# test1.net
KiCad netlist of a schematic drawn in EAGLE
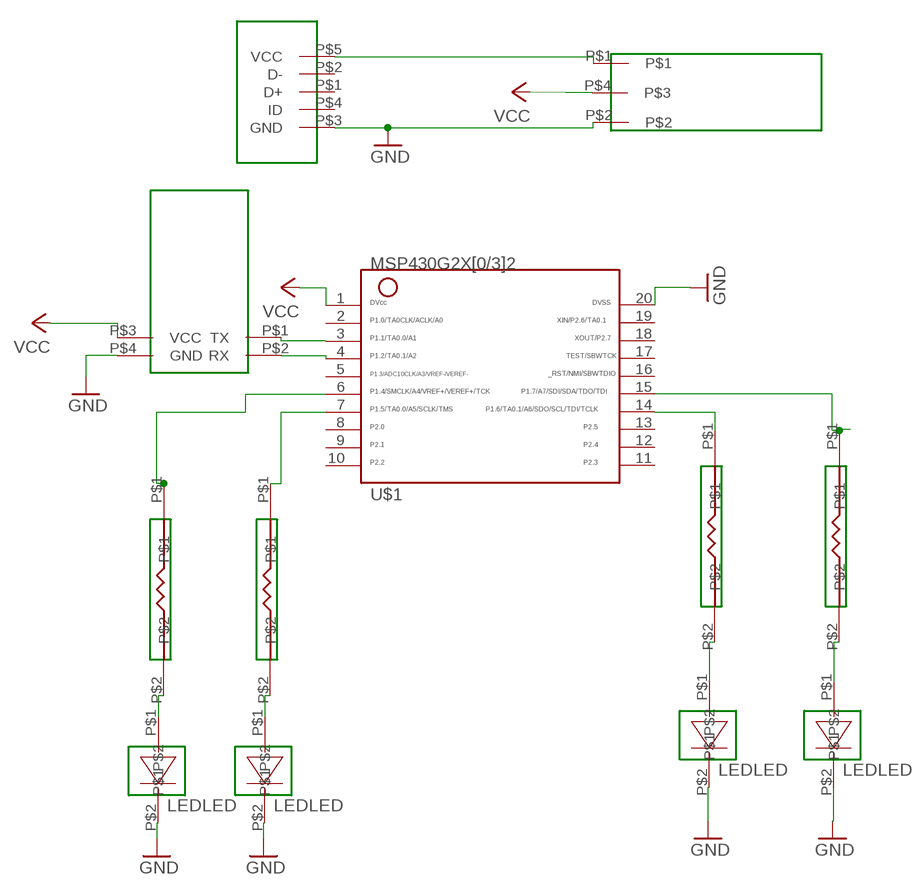
[diagram p0: schematic, sheet 1]

(export (version "E")
  (design (tool "Eeschema 10.0.6"))
  (components
    (comp (ref "U$1")
      (value "MSP430G553MSP430G2553")
      (footprint "eagle-import:MSP430G553")
      (libsource (lib "eagle-import") (part "MSP430G553MSP430G2553"))
    )
    (comp (ref "U$2")
      (value "RN41RN41")
      (footprint "eagle-import:RN41")
      (libsource (lib "eagle-import") (part "RN41RN41"))
    )
    (comp (ref "U$3")
      (value "USBUSB")
      (footprint "eagle-import:USB")
      (libsource (lib "eagle-import") (part "USBUSB"))
    )
    (comp (ref "U$4")
      (value "LEDLED")
      (footprint "eagle-import:LED")
      (libsource (lib "eagle-import") (part "LEDLED"))
    )
    (comp (ref "U$5")
      (value "LEDLED")
      (footprint "eagle-import:LED")
      (libsource (lib "eagle-import") (part "LEDLED"))
    )
    (comp (ref "U$6")
      (value "LEDLED")
      (footprint "eagle-import:LED")
      (libsource (lib "eagle-import") (part "LEDLED"))
    )
    (comp (ref "U$7")
      (value "LEDLED")
      (footprint "eagle-import:LED")
      (libsource (lib "eagle-import") (part "LEDLED"))
    )
    (comp (ref "U$8")
      (value "LMC3V3LMC3V3")
      (footprint "eagle-import:LMC3V3")
      (libsource (lib "eagle-import") (part "LMC3V3LMC3V3"))
    )
    (comp (ref "U$9")
      (value "1KOHM1KOHM")
      (footprint "eagle-import:1KOHM")
      (libsource (lib "eagle-import") (part "1KOHM1KOHM"))
    )
    (comp (ref "U$10")
      (value "1KOHM1KOHM")
      (footprint "eagle-import:1KOHM")
      (libsource (lib "eagle-import") (part "1KOHM1KOHM"))
    )
    (comp (ref "U$11")
      (value "1KOHM1KOHM")
      (footprint "eagle-import:1KOHM")
      (libsource (lib "eagle-import") (part "1KOHM1KOHM"))
    )
    (comp (ref "U$12")
      (value "1KOHM1KOHM")
      (footprint "eagle-import:1KOHM")
      (libsource (lib "eagle-import") (part "1KOHM1KOHM"))
    )
  )
  (nets
    (net (code "1") (name "GND") (class "Default")
      (node (ref "U$1") (pin "20") (pinfunction "20_20") (pintype "bidirectional"))
      (node (ref "U$2") (pin "P$4") (pinfunction "GND_P$4") (pintype "bidirectional"))
      (node (ref "U$3") (pin "P$3") (pinfunction "GND_P$3") (pintype "bidirectional"))
      (node (ref "U$4") (pin "P$2") (pinfunction "P$2_P$2") (pintype "bidirectional"))
      (node (ref "U$5") (pin "P$2") (pinfunction "P$2_P$2") (pintype "bidirectional"))
      (node (ref "U$6") (pin "P$2") (pinfunction "P$2_P$2") (pintype "bidirectional"))
      (node (ref "U$7") (pin "P$2") (pinfunction "P$2_P$2") (pintype "bidirectional"))
      (node (ref "U$8") (pin "P$2") (pinfunction "P$2_P$2") (pintype "bidirectional"))
    )
    (net (code "2") (name "Net-(U$1-Pad6)") (class "Default")
      (node (ref "U$1") (pin "6") (pinfunction "6_6") (pintype "bidirectional"))
      (node (ref "U$9") (pin "P$1") (pinfunction "P$1_P$1") (pintype "bidirectional"))
    )
    (net (code "3") (name "Net-(U$1-Pad7)") (class "Default")
      (node (ref "U$1") (pin "7") (pinfunction "7_7") (pintype "bidirectional"))
      (node (ref "U$10") (pin "P$1") (pinfunction "P$1_P$1") (pintype "bidirectional"))
    )
    (net (code "4") (name "Net-(U$1-Pad14)") (class "Default")
      (node (ref "U$1") (pin "14") (pinfunction "14_14") (pintype "bidirectional"))
      (node (ref "U$11") (pin "P$1") (pinfunction "P$1_P$1") (pintype "bidirectional"))
    )
    (net (code "5") (name "Net-(U$1-Pad15)") (class "Default")
      (node (ref "U$1") (pin "15") (pinfunction "15_15") (pintype "bidirectional"))
      (node (ref "U$12") (pin "P$1") (pinfunction "P$1_P$1") (pintype "bidirectional"))
    )
    (net (code "6") (name "Net-(U$2-RX)") (class "Default")
      (node (ref "U$1") (pin "4") (pinfunction "4_4") (pintype "bidirectional"))
      (node (ref "U$2") (pin "P$2") (pinfunction "RX_P$2") (pintype "bidirectional"))
    )
    (net (code "7") (name "Net-(U$2-TX)") (class "Default")
      (node (ref "U$1") (pin "3") (pinfunction "3_3") (pintype "bidirectional"))
      (node (ref "U$2") (pin "P$1") (pinfunction "TX_P$1") (pintype "bidirectional"))
    )
    (net (code "8") (name "Net-(U$3-VCC)") (class "Default")
      (node (ref "U$3") (pin "P$5") (pinfunction "VCC_P$5") (pintype "bidirectional"))
      (node (ref "U$8") (pin "P$1") (pinfunction "P$1_P$1") (pintype "bidirectional"))
    )
    (net (code "9") (name "Net-(U$4-PadP$1)") (class "Default")
      (node (ref "U$4") (pin "P$1") (pinfunction "P$1_P$1") (pintype "bidirectional"))
      (node (ref "U$9") (pin "P$2") (pinfunction "P$2_P$2") (pintype "bidirectional"))
    )
    (net (code "10") (name "Net-(U$10-PadP$2)") (class "Default")
      (node (ref "U$10") (pin "P$2") (pinfunction "P$2_P$2") (pintype "bidirectional"))
      (node (ref "U$5") (pin "P$1") (pinfunction "P$1_P$1") (pintype "bidirectional"))
    )
    (net (code "11") (name "Net-(U$11-PadP$2)") (class "Default")
      (node (ref "U$11") (pin "P$2") (pinfunction "P$2_P$2") (pintype "bidirectional"))
      (node (ref "U$6") (pin "P$1") (pinfunction "P$1_P$1") (pintype "bidirectional"))
    )
    (net (code "12") (name "Net-(U$12-PadP$2)") (class "Default")
      (node (ref "U$12") (pin "P$2") (pinfunction "P$2_P$2") (pintype "bidirectional"))
      (node (ref "U$7") (pin "P$1") (pinfunction "P$1_P$1") (pintype "bidirectional"))
    )
    (net (code "13") (name "VCC") (class "Default")
      (node (ref "U$1") (pin "1") (pinfunction "1_1") (pintype "bidirectional"))
      (node (ref "U$2") (pin "P$3") (pinfunction "VCC_P$3") (pintype "bidirectional"))
      (node (ref "U$8") (pin "P$4") (pinfunction "P$3_P$4") (pintype "bidirectional"))
    )
    (net (code "14") (name "unconnected-(U$1-Pad2)") (class "Default")
      (node (ref "U$1") (pin "2") (pinfunction "2_2") (pintype "bidirectional"))
    )
    (net (code "15") (name "unconnected-(U$1-Pad5)") (class "Default")
      (node (ref "U$1") (pin "5") (pinfunction "5_5") (pintype "bidirectional"))
    )
    (net (code "16") (name "unconnected-(U$1-Pad8)") (class "Default")
      (node (ref "U$1") (pin "8") (pinfunction "8_8") (pintype "bidirectional"))
    )
    (net (code "17") (name "unconnected-(U$1-Pad9)") (class "Default")
      (node (ref "U$1") (pin "9") (pinfunction "9_9") (pintype "bidirectional"))
    )
    (net (code "18") (name "unconnected-(U$1-Pad10)") (class "Default")
      (node (ref "U$1") (pin "10") (pinfunction "10_10") (pintype "bidirectional"))
    )
    (net (code "19") (name "unconnected-(U$1-Pad11)") (class "Default")
      (node (ref "U$1") (pin "11") (pinfunction "11_11") (pintype "bidirectional"))
    )
    (net (code "20") (name "unconnected-(U$1-Pad12)") (class "Default")
      (node (ref "U$1") (pin "12") (pinfunction "12_12") (pintype "bidirectional"))
    )
    (net (code "21") (name "unconnected-(U$1-Pad13)") (class "Default")
      (node (ref "U$1") (pin "13") (pinfunction "13_13") (pintype "bidirectional"))
    )
    (net (code "22") (name "unconnected-(U$1-Pad16)") (class "Default")
      (node (ref "U$1") (pin "16") (pinfunction "16_16") (pintype "bidirectional"))
    )
    (net (code "23") (name "unconnected-(U$1-Pad17)") (class "Default")
      (node (ref "U$1") (pin "17") (pinfunction "17_17") (pintype "bidirectional"))
    )
    (net (code "24") (name "unconnected-(U$1-Pad18)") (class "Default")
      (node (ref "U$1") (pin "18") (pinfunction "18_18") (pintype "bidirectional"))
    )
    (net (code "25") (name "unconnected-(U$1-Pad19)") (class "Default")
      (node (ref "U$1") (pin "19") (pinfunction "19_19") (pintype "bidirectional"))
    )
    (net (code "26") (name "unconnected-(U$3-D+-PadP$1)") (class "Default")
      (node (ref "U$3") (pin "P$1") (pinfunction "D+_P$1") (pintype "bidirectional"))
    )
    (net (code "27") (name "unconnected-(U$3-D--PadP$2)") (class "Default")
      (node (ref "U$3") (pin "P$2") (pinfunction "D-_P$2") (pintype "bidirectional"))
    )
    (net (code "28") (name "unconnected-(U$3-ID-PadP$4)") (class "Default")
      (node (ref "U$3") (pin "P$4") (pinfunction "ID_P$4") (pintype "bidirectional"))
    )
  )
)
